# Heartrate_Monitor_Internal.net
KiCad netlist of a schematic drawn in Altium Designer
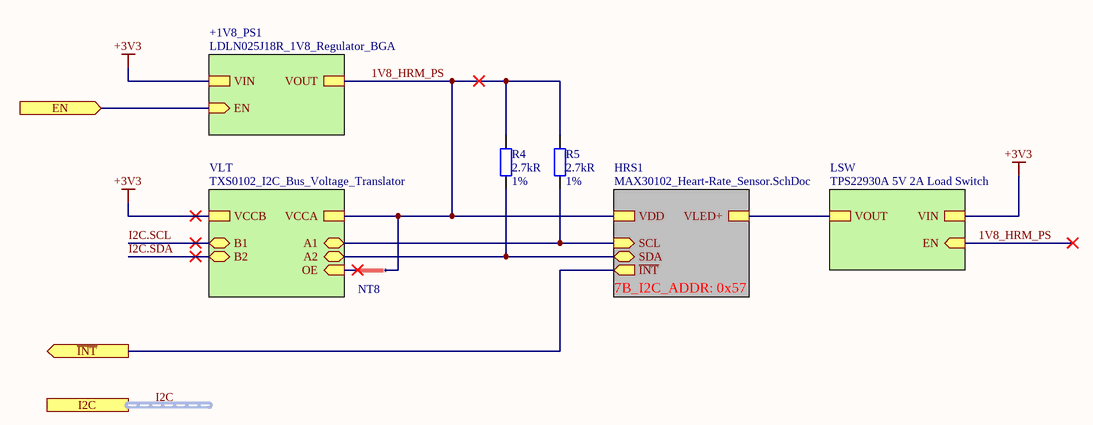
[diagram p0: Heartrate_Monitor_Internal.SchDoc]

(export (version "E")
  (design (tool "Eeschema 10.0.6"))
  (components
    (comp (ref "NT8")
      (value "Net Tie")
      (footprint "Net Tie 6x30mil")
      (libsource (lib "BLDC_Motor_Driver") (part "Net Tie Line"))
    )
    (comp (ref "R4")
      (value "RES SMD 2.7K OHM 1% 1/16W 0402")
      (footprint "R0402")
      (description "2.7 kOhms ±1% 0.063W, 1/16W Chip Resistor 0402 (1005 Metric) Moisture Resistant Thick Film")
      (fields
        (field (name "MANUFACTURER PART NUMBER") "RC0402FR-072K7L")
        (field (name "MANUFACTURER") "Yageo")
        (field (name "RESISTANCE") "2.7kR")
        (field (name "TOLERANCE") "1%")
      )
      (libsource (lib "resistors_smd") (part "RES SMD 2.7K OHM 1% 1/16W 0402"))
    )
    (comp (ref "R5")
      (value "RES SMD 2.7K OHM 1% 1/16W 0402")
      (footprint "R0402")
      (description "2.7 kOhms ±1% 0.063W, 1/16W Chip Resistor 0402 (1005 Metric) Moisture Resistant Thick Film")
      (fields
        (field (name "MANUFACTURER PART NUMBER") "RC0402FR-072K7L")
        (field (name "MANUFACTURER") "Yageo")
        (field (name "RESISTANCE") "2.7kR")
        (field (name "TOLERANCE") "1%")
      )
      (libsource (lib "resistors_smd") (part "RES SMD 2.7K OHM 1% 1/16W 0402"))
    )
  )
  (nets
    (net (code "3") (name "/1V8_HRM_PS") (class "Default")
      (node (ref "NT8") (pin "2") (pintype "passive"))
      (node (ref "R4") (pin "2") (pinfunction "2_2") (pintype "passive"))
      (node (ref "R5") (pin "2") (pinfunction "2_2") (pintype "passive"))
    )
    (net (code "4") (name "/A1") (class "Default")
      (node (ref "R5") (pin "1") (pinfunction "1_1") (pintype "passive"))
    )
    (net (code "5") (name "/A2") (class "Default")
      (node (ref "R4") (pin "1") (pinfunction "1_1") (pintype "passive"))
    )
    (net (code "10") (name "/OE") (class "Default")
      (node (ref "NT8") (pin "1") (pintype "passive+no_connect"))
    )
  )
)
